# Top_Level.net
KiCad netlist of a schematic drawn in Altium Designer
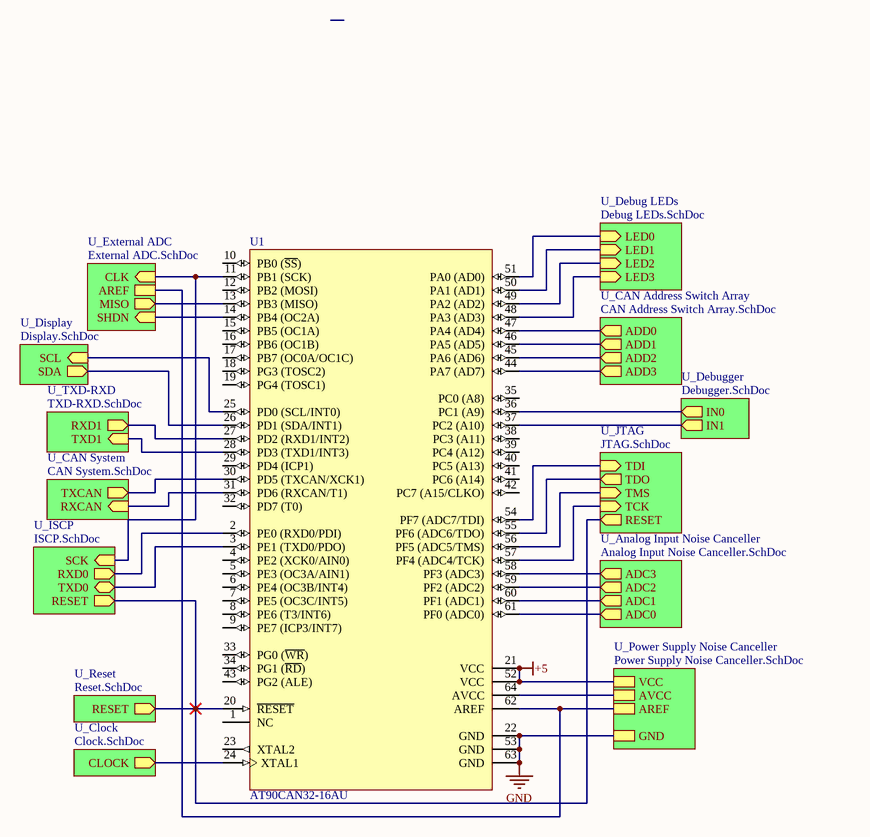
[diagram p0: Top Level.SchDoc]

(export (version "E")
  (design (tool "Eeschema 10.0.6"))
  (components
    (comp (ref "U1")
      (value "AT90CAN32-16AU")
      (footprint "64A_N")
      (libsource (lib "Altium Content Vault") (part "MC-8B-AT90CAN32-SQ64"))
    )
  )
  (nets
    (net (code "1") (name "+5") (class "Default")
      (node (ref "U1") (pin "21") (pinfunction "VCC_21") (pintype "power_in"))
      (node (ref "U1") (pin "52") (pinfunction "VCC_52") (pintype "power_in"))
    )
    (net (code "2") (name "/ADC0") (class "Default")
      (node (ref "U1") (pin "61") (pinfunction "PF0_(ADC0)_61") (pintype "bidirectional"))
    )
    (net (code "3") (name "/ADC1") (class "Default")
      (node (ref "U1") (pin "60") (pinfunction "PF1_(ADC1)_60") (pintype "bidirectional"))
    )
    (net (code "4") (name "/ADC2") (class "Default")
      (node (ref "U1") (pin "59") (pinfunction "PF2_(ADC2)_59") (pintype "bidirectional"))
    )
    (net (code "5") (name "/ADC3") (class "Default")
      (node (ref "U1") (pin "58") (pinfunction "PF3_(ADC3)_58") (pintype "bidirectional"))
    )
    (net (code "6") (name "/ADD0") (class "Default")
      (node (ref "U1") (pin "47") (pinfunction "PA4_(AD4)_47") (pintype "bidirectional"))
    )
    (net (code "7") (name "/ADD1") (class "Default")
      (node (ref "U1") (pin "46") (pinfunction "PA5_(AD5)_46") (pintype "bidirectional"))
    )
    (net (code "8") (name "/ADD2") (class "Default")
      (node (ref "U1") (pin "45") (pinfunction "PA6_(AD6)_45") (pintype "bidirectional"))
    )
    (net (code "9") (name "/ADD3") (class "Default")
      (node (ref "U1") (pin "44") (pinfunction "PA7_(AD7)_44") (pintype "bidirectional"))
    )
    (net (code "10") (name "/AREF") (class "Default")
      (node (ref "U1") (pin "62") (pinfunction "AREF_62") (pintype "power_in"))
    )
    (net (code "11") (name "/AVCC") (class "Default")
      (node (ref "U1") (pin "64") (pinfunction "AVCC_64") (pintype "power_in"))
    )
    (net (code "12") (name "/CLK") (class "Default")
      (node (ref "U1") (pin "11") (pinfunction "PB1_(SCK)_11") (pintype "bidirectional"))
    )
    (net (code "13") (name "/CLOCK") (class "Default")
      (node (ref "U1") (pin "24") (pinfunction "XTAL1_24") (pintype "input"))
    )
    (net (code "14") (name "/IN0") (class "Default")
      (node (ref "U1") (pin "36") (pinfunction "PC1_(A9)_36") (pintype "bidirectional"))
    )
    (net (code "15") (name "/IN1") (class "Default")
      (node (ref "U1") (pin "37") (pinfunction "PC2_(A10)_37") (pintype "bidirectional"))
    )
    (net (code "16") (name "/LED0") (class "Default")
      (node (ref "U1") (pin "51") (pinfunction "PA0_(AD0)_51") (pintype "bidirectional"))
    )
    (net (code "17") (name "/LED1") (class "Default")
      (node (ref "U1") (pin "50") (pinfunction "PA1_(AD1)_50") (pintype "bidirectional"))
    )
    (net (code "18") (name "/LED2") (class "Default")
      (node (ref "U1") (pin "49") (pinfunction "PA2_(AD2)_49") (pintype "bidirectional"))
    )
    (net (code "19") (name "/LED3") (class "Default")
      (node (ref "U1") (pin "48") (pinfunction "PA3_(AD3)_48") (pintype "bidirectional"))
    )
    (net (code "20") (name "/MISO") (class "Default")
      (node (ref "U1") (pin "13") (pinfunction "PB3_(MISO)_13") (pintype "bidirectional"))
    )
    (net (code "21") (name "/RESET") (class "Default")
      (node (ref "U1") (pin "20") (pinfunction "~{RESET}_20") (pintype "input+no_connect"))
    )
    (net (code "22") (name "/RXCAN") (class "Default")
      (node (ref "U1") (pin "31") (pinfunction "PD6_(RXCAN/T1)_31") (pintype "bidirectional"))
    )
    (net (code "23") (name "/RXD0") (class "Default")
      (node (ref "U1") (pin "2") (pinfunction "PE0_(RXD0/PDI)_2") (pintype "bidirectional"))
    )
    (net (code "24") (name "/RXD1") (class "Default")
      (node (ref "U1") (pin "27") (pinfunction "PD2_(RXD1/INT2)_27") (pintype "bidirectional"))
    )
    (net (code "25") (name "/SCL") (class "Default")
      (node (ref "U1") (pin "25") (pinfunction "PD0_(SCL/INT0)_25") (pintype "bidirectional"))
    )
    (net (code "26") (name "/SDA") (class "Default")
      (node (ref "U1") (pin "26") (pinfunction "PD1_(SDA/INT1)_26") (pintype "bidirectional"))
    )
    (net (code "27") (name "/SHDN") (class "Default")
      (node (ref "U1") (pin "14") (pinfunction "PB4_(OC2A)_14") (pintype "bidirectional"))
    )
    (net (code "28") (name "/TCK") (class "Default")
      (node (ref "U1") (pin "57") (pinfunction "PF4_(ADC4/TCK)_57") (pintype "bidirectional"))
    )
    (net (code "29") (name "/TDI") (class "Default")
      (node (ref "U1") (pin "54") (pinfunction "PF7_(ADC7/TDI)_54") (pintype "bidirectional"))
    )
    (net (code "30") (name "/TDO") (class "Default")
      (node (ref "U1") (pin "55") (pinfunction "PF6_(ADC6/TDO)_55") (pintype "bidirectional"))
    )
    (net (code "31") (name "/TMS") (class "Default")
      (node (ref "U1") (pin "56") (pinfunction "PF5_(ADC5/TMS)_56") (pintype "bidirectional"))
    )
    (net (code "32") (name "/TXCAN") (class "Default")
      (node (ref "U1") (pin "30") (pinfunction "PD5_(TXCAN/XCK1)_30") (pintype "bidirectional"))
    )
    (net (code "33") (name "/TXD0") (class "Default")
      (node (ref "U1") (pin "3") (pinfunction "PE1_(TXD0/PDO)_3") (pintype "bidirectional"))
    )
    (net (code "34") (name "/TXD1") (class "Default")
      (node (ref "U1") (pin "28") (pinfunction "PD3_(TXD1/INT3)_28") (pintype "bidirectional"))
    )
    (net (code "35") (name "GND") (class "Default")
      (node (ref "U1") (pin "22") (pinfunction "GND_22") (pintype "power_in"))
      (node (ref "U1") (pin "53") (pinfunction "GND_53") (pintype "power_in"))
      (node (ref "U1") (pin "63") (pinfunction "GND_63") (pintype "power_in"))
    )
    (net (code "36") (name "unconnected-(U1-NC-Pad1)") (class "Default")
      (node (ref "U1") (pin "1") (pinfunction "NC_1") (pintype "passive"))
    )
    (net (code "37") (name "unconnected-(U1-PB0_(~{SS})-Pad10)") (class "Default")
      (node (ref "U1") (pin "10") (pinfunction "PB0_(~{SS})_10") (pintype "bidirectional"))
    )
    (net (code "38") (name "unconnected-(U1-PB2_(MOSI)-Pad12)") (class "Default")
      (node (ref "U1") (pin "12") (pinfunction "PB2_(MOSI)_12") (pintype "bidirectional"))
    )
    (net (code "39") (name "unconnected-(U1-PB5_(OC1A)-Pad15)") (class "Default")
      (node (ref "U1") (pin "15") (pinfunction "PB5_(OC1A)_15") (pintype "bidirectional"))
    )
    (net (code "40") (name "unconnected-(U1-PB6_(OC1B)-Pad16)") (class "Default")
      (node (ref "U1") (pin "16") (pinfunction "PB6_(OC1B)_16") (pintype "bidirectional"))
    )
    (net (code "41") (name "unconnected-(U1-PB7_(OC0A{slash}OC1C)-Pad17)") (class "Default")
      (node (ref "U1") (pin "17") (pinfunction "PB7_(OC0A/OC1C)_17") (pintype "bidirectional"))
    )
    (net (code "42") (name "unconnected-(U1-PC0_(A8)-Pad35)") (class "Default")
      (node (ref "U1") (pin "35") (pinfunction "PC0_(A8)_35") (pintype "bidirectional"))
    )
    (net (code "43") (name "unconnected-(U1-PC3_(A11)-Pad38)") (class "Default")
      (node (ref "U1") (pin "38") (pinfunction "PC3_(A11)_38") (pintype "bidirectional"))
    )
    (net (code "44") (name "unconnected-(U1-PC4_(A12)-Pad39)") (class "Default")
      (node (ref "U1") (pin "39") (pinfunction "PC4_(A12)_39") (pintype "bidirectional"))
    )
    (net (code "45") (name "unconnected-(U1-PC5_(A13)-Pad40)") (class "Default")
      (node (ref "U1") (pin "40") (pinfunction "PC5_(A13)_40") (pintype "bidirectional"))
    )
    (net (code "46") (name "unconnected-(U1-PC6_(A14)-Pad41)") (class "Default")
      (node (ref "U1") (pin "41") (pinfunction "PC6_(A14)_41") (pintype "bidirectional"))
    )
    (net (code "47") (name "unconnected-(U1-PC7_(A15{slash}CLKO)-Pad42)") (class "Default")
      (node (ref "U1") (pin "42") (pinfunction "PC7_(A15/CLKO)_42") (pintype "bidirectional"))
    )
    (net (code "48") (name "unconnected-(U1-PD4_(ICP1)-Pad29)") (class "Default")
      (node (ref "U1") (pin "29") (pinfunction "PD4_(ICP1)_29") (pintype "bidirectional"))
    )
    (net (code "49") (name "unconnected-(U1-PD7_(T0)-Pad32)") (class "Default")
      (node (ref "U1") (pin "32") (pinfunction "PD7_(T0)_32") (pintype "bidirectional"))
    )
    (net (code "50") (name "unconnected-(U1-PE2_(XCK0{slash}AIN0)-Pad4)") (class "Default")
      (node (ref "U1") (pin "4") (pinfunction "PE2_(XCK0/AIN0)_4") (pintype "bidirectional"))
    )
    (net (code "51") (name "unconnected-(U1-PE3_(OC3A{slash}AIN1)-Pad5)") (class "Default")
      (node (ref "U1") (pin "5") (pinfunction "PE3_(OC3A/AIN1)_5") (pintype "bidirectional"))
    )
    (net (code "52") (name "unconnected-(U1-PE4_(OC3B{slash}INT4)-Pad6)") (class "Default")
      (node (ref "U1") (pin "6") (pinfunction "PE4_(OC3B/INT4)_6") (pintype "bidirectional"))
    )
    (net (code "53") (name "unconnected-(U1-PE5_(OC3C{slash}INT5)-Pad7)") (class "Default")
      (node (ref "U1") (pin "7") (pinfunction "PE5_(OC3C/INT5)_7") (pintype "bidirectional"))
    )
    (net (code "54") (name "unconnected-(U1-PE6_(T3{slash}INT6)-Pad8)") (class "Default")
      (node (ref "U1") (pin "8") (pinfunction "PE6_(T3/INT6)_8") (pintype "bidirectional"))
    )
    (net (code "55") (name "unconnected-(U1-PE7_(ICP3{slash}INT7)-Pad9)") (class "Default")
      (node (ref "U1") (pin "9") (pinfunction "PE7_(ICP3/INT7)_9") (pintype "bidirectional"))
    )
    (net (code "56") (name "unconnected-(U1-PG0_(~{WR})-Pad33)") (class "Default")
      (node (ref "U1") (pin "33") (pinfunction "PG0_(~{WR})_33") (pintype "bidirectional"))
    )
    (net (code "57") (name "unconnected-(U1-PG1_(~{RD})-Pad34)") (class "Default")
      (node (ref "U1") (pin "34") (pinfunction "PG1_(~{RD})_34") (pintype "bidirectional"))
    )
    (net (code "58") (name "unconnected-(U1-PG2_(ALE)-Pad43)") (class "Default")
      (node (ref "U1") (pin "43") (pinfunction "PG2_(ALE)_43") (pintype "bidirectional"))
    )
    (net (code "59") (name "unconnected-(U1-PG3_(TOSC2)-Pad18)") (class "Default")
      (node (ref "U1") (pin "18") (pinfunction "PG3_(TOSC2)_18") (pintype "bidirectional"))
    )
    (net (code "60") (name "unconnected-(U1-PG4_(TOSC1)-Pad19)") (class "Default")
      (node (ref "U1") (pin "19") (pinfunction "PG4_(TOSC1)_19") (pintype "bidirectional"))
    )
    (net (code "61") (name "unconnected-(U1-XTAL2-Pad23)") (class "Default")
      (node (ref "U1") (pin "23") (pinfunction "XTAL2_23") (pintype "output"))
    )
  )
)
